# UartsAndGPS.net
KiCad netlist of a schematic drawn in Altium Designer
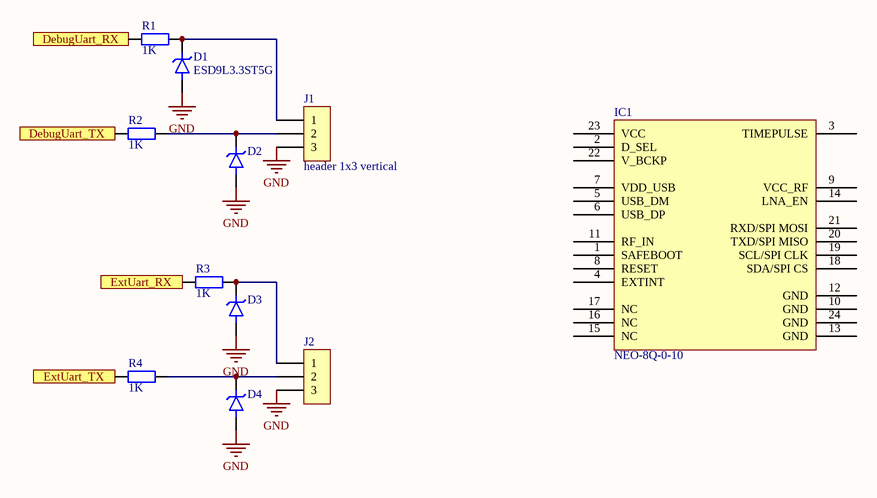
[diagram p0: UartsAndGPS.SchDoc]

(export (version "E")
  (design (tool "Eeschema 10.0.6"))
  (components
    (comp (ref "D1")
      (value "ESD9L3.3ST5G")
      (footprint "SOD923F, NOMINAL")
      (description "TVS DIODE, Unidir, 3.3V/9V, 150mW, SOD-923, ESD9L3.3ST5G, ON SEMICONDUCTOR")
      (fields (field (name "MANUFACTURER") "ON Semiconductor"))
      (libsource (lib "Diodes") (part "ESD9L3.3ST5G"))
    )
    (comp (ref "D2")
      (value "ESD9L3.3ST5G")
      (footprint "SOD923F, NOMINAL")
      (description "TVS DIODE, Unidir, 3.3V/9V, 150mW, SOD-923, ESD9L3.3ST5G, ON SEMICONDUCTOR")
      (fields (field (name "MANUFACTURER") "ON Semiconductor"))
      (libsource (lib "Diodes") (part "ESD9L3.3ST5G"))
    )
    (comp (ref "D3")
      (value "ESD9L3.3ST5G")
      (footprint "SOD923F, NOMINAL")
      (description "TVS DIODE, Unidir, 3.3V/9V, 150mW, SOD-923, ESD9L3.3ST5G, ON SEMICONDUCTOR")
      (fields (field (name "MANUFACTURER") "ON Semiconductor"))
      (libsource (lib "Diodes") (part "ESD9L3.3ST5G"))
    )
    (comp (ref "D4")
      (value "ESD9L3.3ST5G")
      (footprint "SOD923F, NOMINAL")
      (description "TVS DIODE, Unidir, 3.3V/9V, 150mW, SOD-923, ESD9L3.3ST5G, ON SEMICONDUCTOR")
      (fields (field (name "MANUFACTURER") "ON Semiconductor"))
      (libsource (lib "Diodes") (part "ESD9L3.3ST5G"))
    )
    (comp (ref "IC1")
      (value "NEO-8Q-0-10")
      (footprint "NEO-8Q")
      (description "GPS GLONASS module, +-2m, -166dBm, 2.7..3.6Vin")
      (libsource (lib "GPS") (part "NEO-8Q"))
    )
    (comp (ref "J1")
      (value "header 1x3 vertical")
      (footprint "UART_HEADER")
      (libsource (lib "pinheader") (part "header 1x3 vertical"))
    )
    (comp (ref "J2")
      (value "header 1x3 vertical")
      (footprint "UART_HEADER")
      (libsource (lib "pinheader") (part "header 1x3 vertical"))
    )
    (comp (ref "R1")
      (value "1K")
      (footprint "R0603")
      (description "Resistor")
      (fields (field (name "RESISTANCE") "1K"))
      (libsource (lib "Passives") (part "Resistor"))
    )
    (comp (ref "R2")
      (value "1K")
      (footprint "R0603")
      (description "Resistor")
      (fields (field (name "RESISTANCE") "1K"))
      (libsource (lib "Passives") (part "Resistor"))
    )
    (comp (ref "R3")
      (value "1K")
      (footprint "R0603")
      (description "Resistor")
      (fields (field (name "RESISTANCE") "1K"))
      (libsource (lib "Passives") (part "Resistor"))
    )
    (comp (ref "R4")
      (value "1K")
      (footprint "R0603")
      (description "Resistor")
      (fields (field (name "RESISTANCE") "1K"))
      (libsource (lib "Passives") (part "Resistor"))
    )
  )
  (nets
    (net (code "1") (name "/DebugUart_RX") (class "Default")
      (node (ref "R1") (pin "2") (pinfunction "2_2") (pintype "passive"))
    )
    (net (code "2") (name "/DebugUart_TX") (class "Default")
      (node (ref "R2") (pin "2") (pinfunction "2_2") (pintype "passive"))
    )
    (net (code "3") (name "/ExtUart_RX") (class "Default")
      (node (ref "R3") (pin "2") (pinfunction "2_2") (pintype "passive"))
    )
    (net (code "4") (name "/ExtUart_TX") (class "Default")
      (node (ref "R4") (pin "2") (pinfunction "2_2") (pintype "passive"))
    )
    (net (code "5") (name "GND") (class "Default")
      (node (ref "D1") (pin "A") (pinfunction "A_A") (pintype "passive"))
      (node (ref "D2") (pin "A") (pinfunction "A_A") (pintype "passive"))
      (node (ref "D3") (pin "A") (pinfunction "A_A") (pintype "passive"))
      (node (ref "D4") (pin "A") (pinfunction "A_A") (pintype "passive"))
      (node (ref "J1") (pin "3") (pinfunction "3_3") (pintype "passive"))
      (node (ref "J2") (pin "3") (pinfunction "3_3") (pintype "passive"))
    )
    (net (code "6") (name "Net-(D1-PadC)") (class "Default")
      (node (ref "D1") (pin "C") (pinfunction "C_C") (pintype "passive"))
      (node (ref "J1") (pin "1") (pinfunction "1_1") (pintype "passive"))
      (node (ref "R1") (pin "1") (pinfunction "1_1") (pintype "passive"))
    )
    (net (code "7") (name "Net-(D2-PadC)") (class "Default")
      (node (ref "D2") (pin "C") (pinfunction "C_C") (pintype "passive"))
      (node (ref "J1") (pin "2") (pinfunction "2_2") (pintype "passive"))
      (node (ref "R2") (pin "1") (pinfunction "1_1") (pintype "passive"))
    )
    (net (code "8") (name "Net-(D3-PadC)") (class "Default")
      (node (ref "D3") (pin "C") (pinfunction "C_C") (pintype "passive"))
      (node (ref "J2") (pin "1") (pinfunction "1_1") (pintype "passive"))
      (node (ref "R3") (pin "1") (pinfunction "1_1") (pintype "passive"))
    )
    (net (code "9") (name "Net-(D4-PadC)") (class "Default")
      (node (ref "D4") (pin "C") (pinfunction "C_C") (pintype "passive"))
      (node (ref "J2") (pin "2") (pinfunction "2_2") (pintype "passive"))
      (node (ref "R4") (pin "1") (pinfunction "1_1") (pintype "passive"))
    )
    (net (code "10") (name "unconnected-(IC1-D_SEL-Pad2)") (class "Default")
      (node (ref "IC1") (pin "2") (pinfunction "D_SEL_2") (pintype "passive"))
    )
    (net (code "11") (name "unconnected-(IC1-EXTINT-Pad4)") (class "Default")
      (node (ref "IC1") (pin "4") (pinfunction "EXTINT_4") (pintype "passive"))
    )
    (net (code "12") (name "unconnected-(IC1-GND-Pad10)") (class "Default")
      (node (ref "IC1") (pin "10") (pinfunction "GND_10") (pintype "passive"))
    )
    (net (code "13") (name "unconnected-(IC1-GND-Pad12)") (class "Default")
      (node (ref "IC1") (pin "12") (pinfunction "GND_12") (pintype "passive"))
    )
    (net (code "14") (name "unconnected-(IC1-GND-Pad13)") (class "Default")
      (node (ref "IC1") (pin "13") (pinfunction "GND_13") (pintype "passive"))
    )
    (net (code "15") (name "unconnected-(IC1-GND-Pad24)") (class "Default")
      (node (ref "IC1") (pin "24") (pinfunction "GND_24") (pintype "passive"))
    )
    (net (code "16") (name "unconnected-(IC1-LNA_EN-Pad14)") (class "Default")
      (node (ref "IC1") (pin "14") (pinfunction "LNA_EN_14") (pintype "passive"))
    )
    (net (code "17") (name "unconnected-(IC1-NC-Pad15)") (class "Default")
      (node (ref "IC1") (pin "15") (pinfunction "NC_15") (pintype "passive"))
    )
    (net (code "18") (name "unconnected-(IC1-NC-Pad16)") (class "Default")
      (node (ref "IC1") (pin "16") (pinfunction "NC_16") (pintype "passive"))
    )
    (net (code "19") (name "unconnected-(IC1-NC-Pad17)") (class "Default")
      (node (ref "IC1") (pin "17") (pinfunction "NC_17") (pintype "passive"))
    )
    (net (code "20") (name "unconnected-(IC1-RESET-Pad8)") (class "Default")
      (node (ref "IC1") (pin "8") (pinfunction "RESET_8") (pintype "passive"))
    )
    (net (code "21") (name "unconnected-(IC1-RF_IN-Pad11)") (class "Default")
      (node (ref "IC1") (pin "11") (pinfunction "RF_IN_11") (pintype "passive"))
    )
    (net (code "22") (name "unconnected-(IC1-RXD{slash}SPI_MOSI-Pad21)") (class "Default")
      (node (ref "IC1") (pin "21") (pinfunction "RXD/SPI_MOSI_21") (pintype "passive"))
    )
    (net (code "23") (name "unconnected-(IC1-SAFEBOOT-Pad1)") (class "Default")
      (node (ref "IC1") (pin "1") (pinfunction "SAFEBOOT_1") (pintype "passive"))
    )
    (net (code "24") (name "unconnected-(IC1-SCL{slash}SPI_CLK-Pad19)") (class "Default")
      (node (ref "IC1") (pin "19") (pinfunction "SCL/SPI_CLK_19") (pintype "passive"))
    )
    (net (code "25") (name "unconnected-(IC1-SDA{slash}SPI_CS-Pad18)") (class "Default")
      (node (ref "IC1") (pin "18") (pinfunction "SDA/SPI_CS_18") (pintype "passive"))
    )
    (net (code "26") (name "unconnected-(IC1-TIMEPULSE-Pad3)") (class "Default")
      (node (ref "IC1") (pin "3") (pinfunction "TIMEPULSE_3") (pintype "passive"))
    )
    (net (code "27") (name "unconnected-(IC1-TXD{slash}SPI_MISO-Pad20)") (class "Default")
      (node (ref "IC1") (pin "20") (pinfunction "TXD/SPI_MISO_20") (pintype "passive"))
    )
    (net (code "28") (name "unconnected-(IC1-USB_DM-Pad5)") (class "Default")
      (node (ref "IC1") (pin "5") (pinfunction "USB_DM_5") (pintype "passive"))
    )
    (net (code "29") (name "unconnected-(IC1-USB_DP-Pad6)") (class "Default")
      (node (ref "IC1") (pin "6") (pinfunction "USB_DP_6") (pintype "passive"))
    )
    (net (code "30") (name "unconnected-(IC1-VCC-Pad23)") (class "Default")
      (node (ref "IC1") (pin "23") (pinfunction "VCC_23") (pintype "passive"))
    )
    (net (code "31") (name "unconnected-(IC1-VCC_RF-Pad9)") (class "Default")
      (node (ref "IC1") (pin "9") (pinfunction "VCC_RF_9") (pintype "passive"))
    )
    (net (code "32") (name "unconnected-(IC1-VDD_USB-Pad7)") (class "Default")
      (node (ref "IC1") (pin "7") (pinfunction "VDD_USB_7") (pintype "passive"))
    )
    (net (code "33") (name "unconnected-(IC1-V_BCKP-Pad22)") (class "Default")
      (node (ref "IC1") (pin "22") (pinfunction "V_BCKP_22") (pintype "passive"))
    )
  )
)
